# ProProject_Access_Control_Interface_2024.net
KiCad netlist of a schematic drawn in EasyEDA Pro
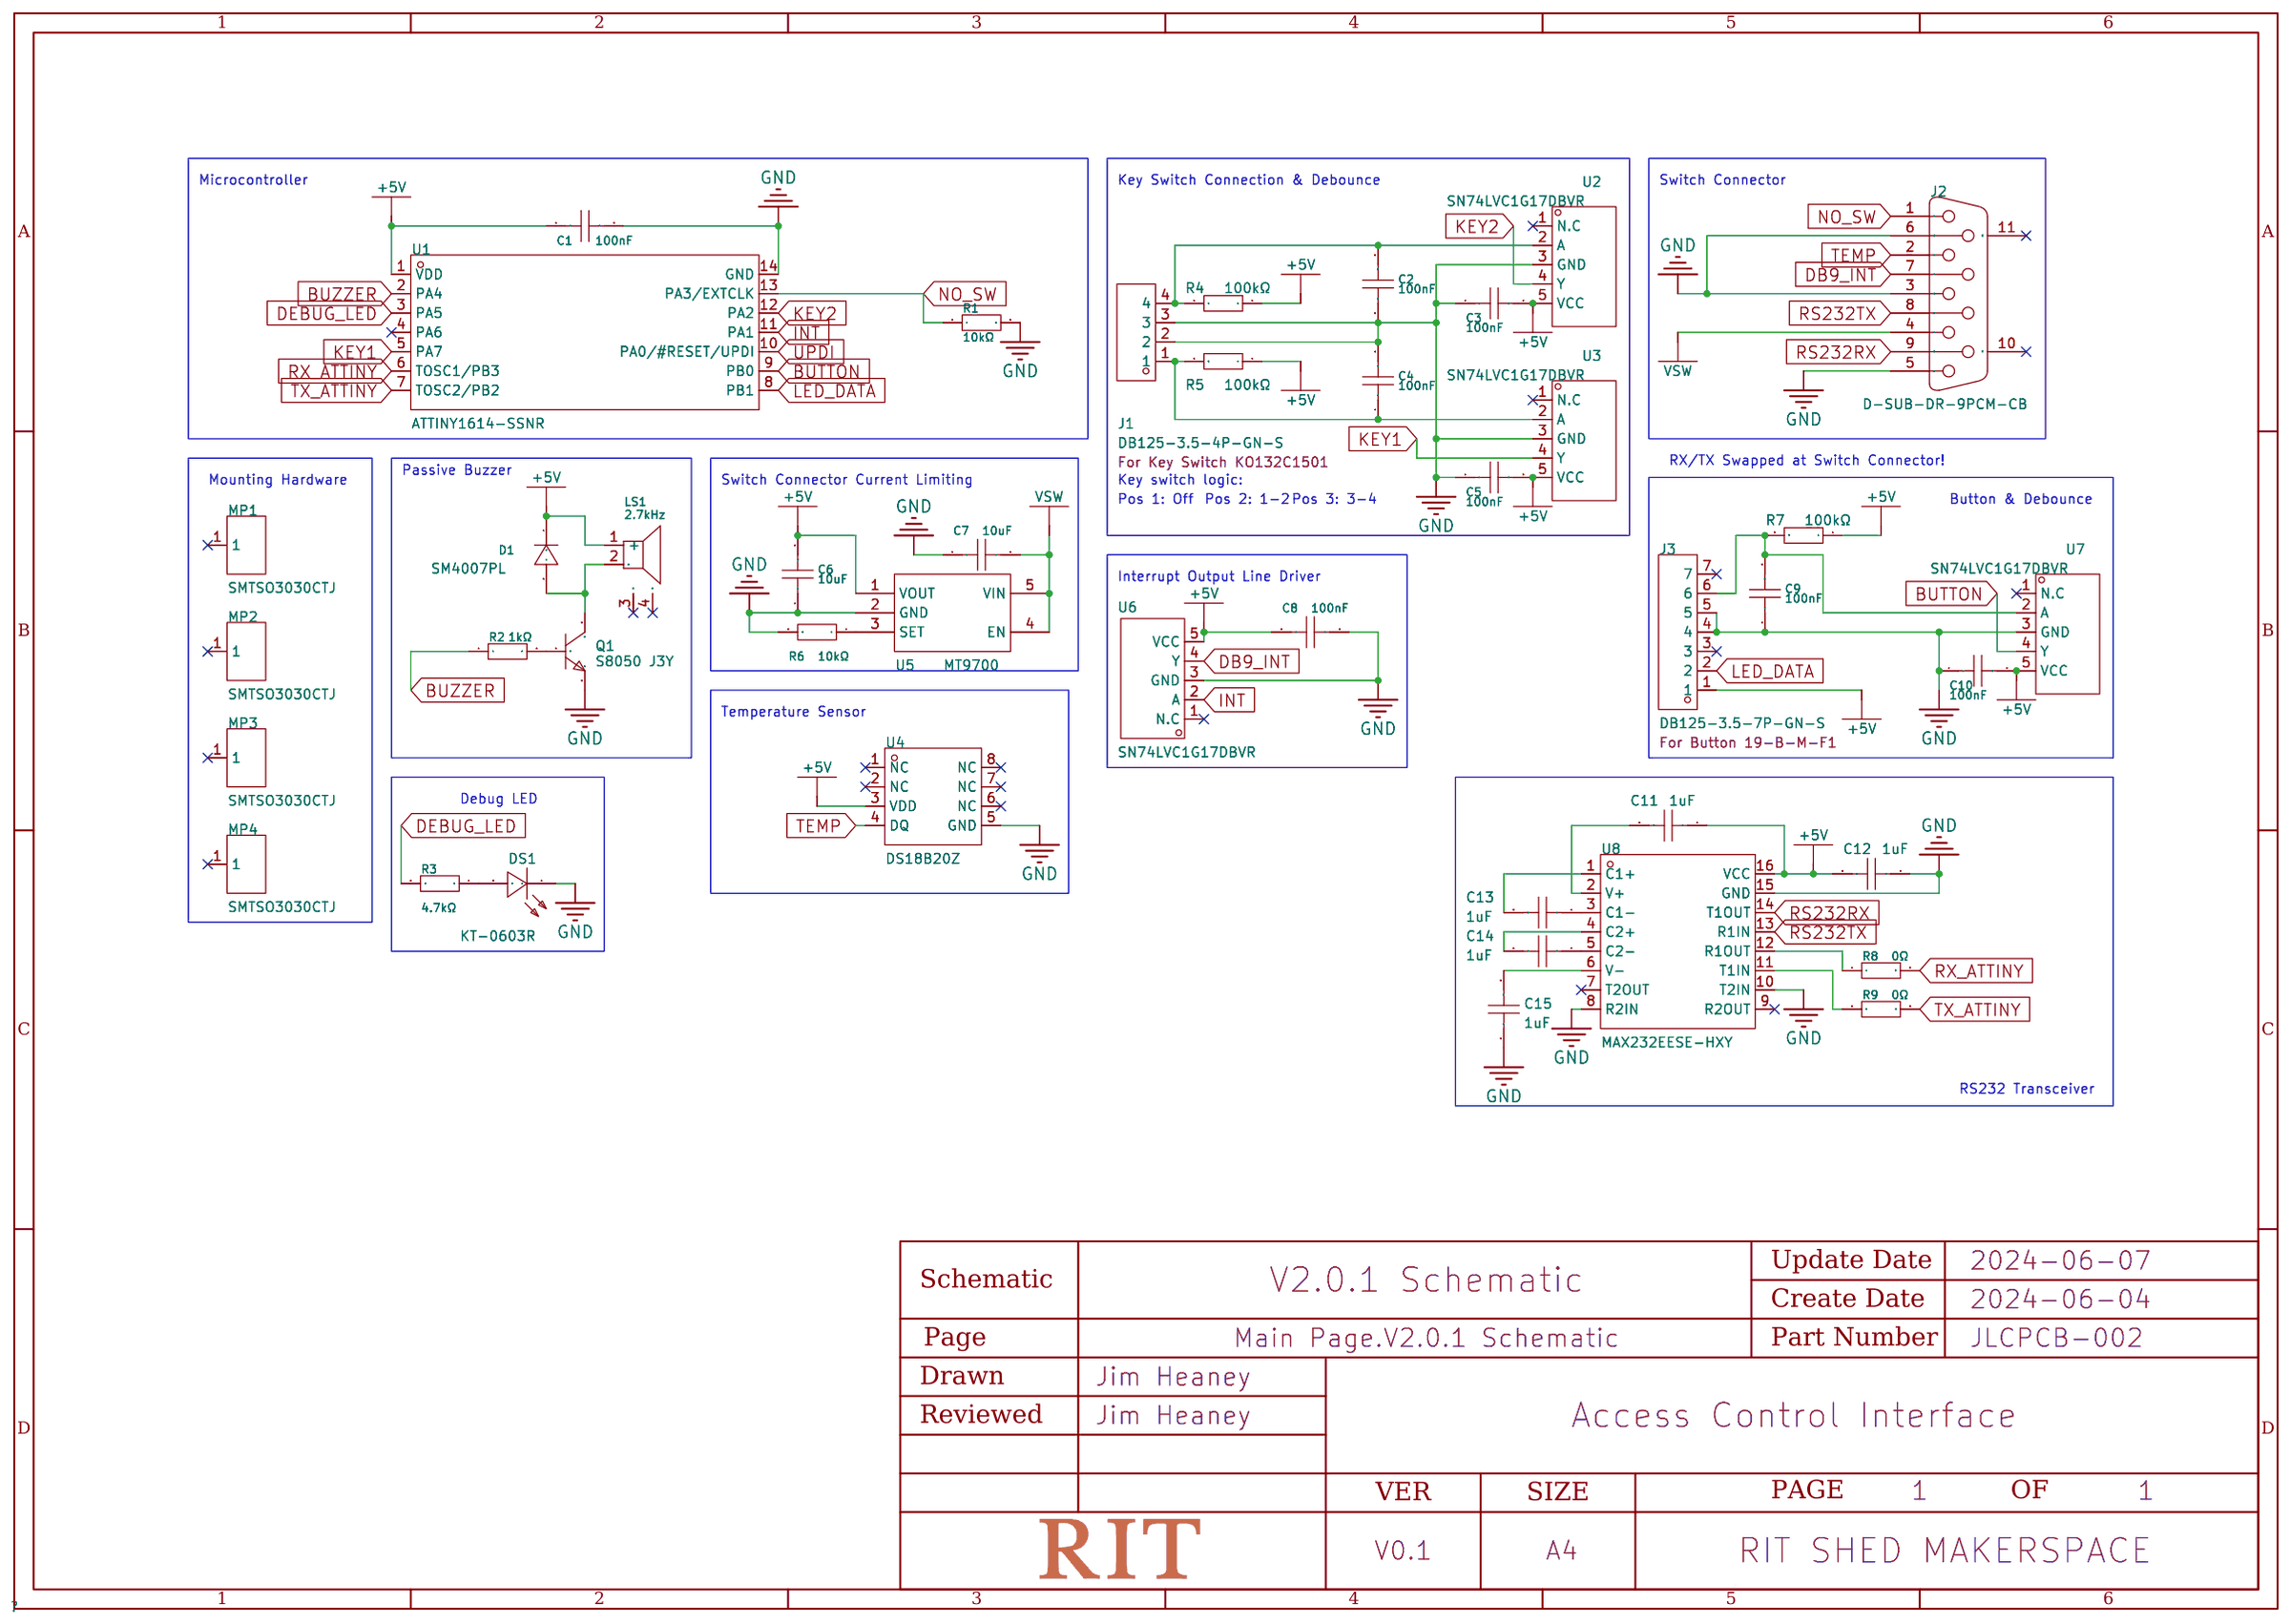
[diagram p0: schematic sheet]

(export (version "E")
  (design (tool "Eeschema 10.0.6"))
  (components
    (comp (ref "C1")
      (value "100nF")
      (footprint "easyedapro:C0603")
      (fields
        (field (name "Manufacturer Part") "CC0603KRX7R9BB104")
        (field (name "Manufacturer") "YAGEO(国巨)")
      )
      (libsource (lib "easyedapro") (part "CC0603KRX7R9BB104"))
    )
    (comp (ref "C2")
      (value "100nF")
      (footprint "easyedapro:C0603")
      (fields
        (field (name "Manufacturer Part") "CC0603KRX7R9BB104")
        (field (name "Manufacturer") "YAGEO(国巨)")
      )
      (libsource (lib "easyedapro") (part "CC0603KRX7R9BB104"))
    )
    (comp (ref "C3")
      (value "100nF")
      (footprint "easyedapro:C0603")
      (fields
        (field (name "Manufacturer Part") "CC0603KRX7R9BB104")
        (field (name "Manufacturer") "YAGEO(国巨)")
      )
      (libsource (lib "easyedapro") (part "CC0603KRX7R9BB104"))
    )
    (comp (ref "C4")
      (value "100nF")
      (footprint "easyedapro:C0603")
      (fields
        (field (name "Manufacturer Part") "CC0603KRX7R9BB104")
        (field (name "Manufacturer") "YAGEO(国巨)")
      )
      (libsource (lib "easyedapro") (part "CC0603KRX7R9BB104"))
    )
    (comp (ref "C5")
      (value "100nF")
      (footprint "easyedapro:C0603")
      (fields
        (field (name "Manufacturer Part") "CC0603KRX7R9BB104")
        (field (name "Manufacturer") "YAGEO(国巨)")
      )
      (libsource (lib "easyedapro") (part "CC0603KRX7R9BB104"))
    )
    (comp (ref "C6")
      (value "10uF")
      (footprint "easyedapro:C0603")
      (fields
        (field (name "Manufacturer Part") "CL10A106MA8NRNC")
        (field (name "Manufacturer") "SAMSUNG(三星)")
      )
      (libsource (lib "easyedapro") (part "CL10A106MA8NRNC"))
    )
    (comp (ref "C7")
      (value "10uF")
      (footprint "easyedapro:C0603")
      (fields
        (field (name "Manufacturer Part") "CL10A106MA8NRNC")
        (field (name "Manufacturer") "SAMSUNG(三星)")
      )
      (libsource (lib "easyedapro") (part "CL10A106MA8NRNC"))
    )
    (comp (ref "C8")
      (value "100nF")
      (footprint "easyedapro:C0603")
      (fields
        (field (name "Manufacturer Part") "CC0603KRX7R9BB104")
        (field (name "Manufacturer") "YAGEO(国巨)")
      )
      (libsource (lib "easyedapro") (part "CC0603KRX7R9BB104"))
    )
    (comp (ref "C9")
      (value "100nF")
      (footprint "easyedapro:C0603")
      (fields
        (field (name "Manufacturer Part") "CC0603KRX7R9BB104")
        (field (name "Manufacturer") "YAGEO(国巨)")
      )
      (libsource (lib "easyedapro") (part "CC0603KRX7R9BB104"))
    )
    (comp (ref "C10")
      (value "100nF")
      (footprint "easyedapro:C0603")
      (fields
        (field (name "Manufacturer Part") "CC0603KRX7R9BB104")
        (field (name "Manufacturer") "YAGEO(国巨)")
      )
      (libsource (lib "easyedapro") (part "CC0603KRX7R9BB104"))
    )
    (comp (ref "C11")
      (value "1uF")
      (footprint "easyedapro:C0603")
      (fields
        (field (name "Manufacturer Part") "CL10A105KB8NNNC")
        (field (name "Manufacturer") "SAMSUNG(三星)")
      )
      (libsource (lib "easyedapro") (part "CL10A105KB8NNNC"))
    )
    (comp (ref "C12")
      (value "1uF")
      (footprint "easyedapro:C0603")
      (fields
        (field (name "Manufacturer Part") "CL10A105KB8NNNC")
        (field (name "Manufacturer") "SAMSUNG(三星)")
      )
      (libsource (lib "easyedapro") (part "CL10A105KB8NNNC"))
    )
    (comp (ref "C13")
      (value "1uF")
      (footprint "easyedapro:C0603")
      (fields
        (field (name "Manufacturer Part") "CL10A105KB8NNNC")
        (field (name "Manufacturer") "SAMSUNG(三星)")
      )
      (libsource (lib "easyedapro") (part "CL10A105KB8NNNC"))
    )
    (comp (ref "C14")
      (value "1uF")
      (footprint "easyedapro:C0603")
      (fields
        (field (name "Manufacturer Part") "CL10A105KB8NNNC")
        (field (name "Manufacturer") "SAMSUNG(三星)")
      )
      (libsource (lib "easyedapro") (part "CL10A105KB8NNNC"))
    )
    (comp (ref "C15")
      (value "1uF")
      (footprint "easyedapro:C0603")
      (fields
        (field (name "Manufacturer Part") "CL10A105KB8NNNC")
        (field (name "Manufacturer") "SAMSUNG(三星)")
      )
      (libsource (lib "easyedapro") (part "CL10A105KB8NNNC"))
    )
    (comp (ref "D1")
      (value "SM4007PL")
      (footprint "easyedapro:SOD-123F_L2.8-W1.8-LS3.7-RD")
      (fields (field (name "Manufacturer") "MDD"))
      (libsource (lib "easyedapro") (part "SM4007PL"))
    )
    (comp (ref "DS1")
      (value "KT-0603R")
      (footprint "easyedapro:LED0603-RD")
      (fields (field (name "Manufacturer") "KENTO"))
      (libsource (lib "easyedapro") (part "KT-0603R"))
    )
    (comp (ref "J1")
      (value "DB125-3.5-4P-GN-S")
      (footprint "easyedapro:CONN-TH_DB125-3.5-4P-GN")
      (description "For Key Switch KO132C1501")
      (fields (field (name "Manufacturer") "DORABO(地博电气)"))
      (libsource (lib "easyedapro") (part "DB125-3.5-4P-GN"))
    )
    (comp (ref "J2")
      (value "D-SUB-DR-9PCM-CB")
      (footprint "easyedapro:DB9-TH_ID09S33E4GV00LF")
      (fields (field (name "Manufacturer") "XUNPU(讯普)"))
      (libsource (lib "easyedapro") (part "D-SUB-DR-9PCM-CB"))
    )
    (comp (ref "J3")
      (value "DB125-3.5-7P-GN-S")
      (footprint "easyedapro:CONN-TH_7P-P3.50_DORABO_DB125-3.5-7P-GN-S")
      (description "For Button 19-B-M-F1")
      (fields (field (name "Manufacturer") "DORABO(地博电气)"))
      (libsource (lib "easyedapro") (part "DB125-3.5-7P-GN-S"))
    )
    (comp (ref "LS1")
      (value "2.7kHz")
      (footprint "easyedapro:BUZ-SMD_4P-L8.5-W8.5-P8.50-TL")
      (fields (field (name "Manufacturer Part") "MLT-8540") (field (name "Manufacturer") "华能"))
      (libsource (lib "easyedapro") (part "MLT-8540"))
    )
    (comp (ref "MP1")
      (value "SMTSO3030CTJ")
      (footprint "easyedapro:SMD_BD5.6-D4.1")
      (description "specifications:M3X3 surface treatment:镀锡 Product Description:- material quality:-")
      (fields (field (name "Manufacturer") "Sinhoo(雄和远景)"))
      (libsource (lib "easyedapro") (part "SMTSO3030CTJ"))
    )
    (comp (ref "MP2")
      (value "SMTSO3030CTJ")
      (footprint "easyedapro:SMD_BD5.6-D4.1")
      (description "specifications:M3X3 surface treatment:镀锡 Product Description:- material quality:-")
      (fields (field (name "Manufacturer") "Sinhoo(雄和远景)"))
      (libsource (lib "easyedapro") (part "SMTSO3030CTJ"))
    )
    (comp (ref "MP3")
      (value "SMTSO3030CTJ")
      (footprint "easyedapro:SMD_BD5.6-D4.1")
      (description "specifications:M3X3 surface treatment:镀锡 Product Description:- material quality:-")
      (fields (field (name "Manufacturer") "Sinhoo(雄和远景)"))
      (libsource (lib "easyedapro") (part "SMTSO3030CTJ"))
    )
    (comp (ref "MP4")
      (value "SMTSO3030CTJ")
      (footprint "easyedapro:SMD_BD5.6-D4.1")
      (description "specifications:M3X3 surface treatment:镀锡 Product Description:- material quality:-")
      (fields (field (name "Manufacturer") "Sinhoo(雄和远景)"))
      (libsource (lib "easyedapro") (part "SMTSO3030CTJ"))
    )
    (comp (ref "Q1")
      (value "S8050 J3Y")
      (footprint "easyedapro:SOT-23-3_L3.0-W1.7-P0.95-LS2.9-BR")
      (fields (field (name "Manufacturer") "CJ(江苏长电/长晶)"))
      (libsource (lib "easyedapro") (part "S8050_C2146"))
    )
    (comp (ref "R1")
      (value "10kΩ")
      (footprint "easyedapro:R0603")
      (fields
        (field (name "Manufacturer Part") "0603WAF1002T5E")
        (field (name "Manufacturer") "UNI-ROYAL(厚声)")
      )
      (libsource (lib "easyedapro") (part "0603WAF1002T5E"))
    )
    (comp (ref "R2")
      (value "1kΩ")
      (footprint "easyedapro:R0603")
      (fields
        (field (name "Manufacturer Part") "0603WAF1001T5E")
        (field (name "Manufacturer") "UNI-ROYAL(厚声)")
      )
      (libsource (lib "easyedapro") (part "0603WAF1001T5E"))
    )
    (comp (ref "R3")
      (value "4.7kΩ")
      (footprint "easyedapro:R0603")
      (fields
        (field (name "Manufacturer Part") "0603WAF4701T5E")
        (field (name "Manufacturer") "UNI-ROYAL(厚声)")
      )
      (libsource (lib "easyedapro") (part "0603WAF4701T5E"))
    )
    (comp (ref "R4")
      (value "100kΩ")
      (footprint "easyedapro:R0603")
      (fields
        (field (name "Manufacturer Part") "0603WAF1003T5E")
        (field (name "Manufacturer") "UNI-ROYAL(厚声)")
      )
      (libsource (lib "easyedapro") (part "0603WAF1003T5E"))
    )
    (comp (ref "R5")
      (value "100kΩ")
      (footprint "easyedapro:R0603")
      (fields
        (field (name "Manufacturer Part") "0603WAF1003T5E")
        (field (name "Manufacturer") "UNI-ROYAL(厚声)")
      )
      (libsource (lib "easyedapro") (part "0603WAF1003T5E"))
    )
    (comp (ref "R6")
      (value "10kΩ")
      (footprint "easyedapro:R0603")
      (fields
        (field (name "Manufacturer Part") "0603WAF1002T5E")
        (field (name "Manufacturer") "UNI-ROYAL(厚声)")
      )
      (libsource (lib "easyedapro") (part "0603WAF1002T5E"))
    )
    (comp (ref "R7")
      (value "100kΩ")
      (footprint "easyedapro:R0603")
      (fields
        (field (name "Manufacturer Part") "0603WAF1003T5E")
        (field (name "Manufacturer") "UNI-ROYAL(厚声)")
      )
      (libsource (lib "easyedapro") (part "0603WAF1003T5E"))
    )
    (comp (ref "R8")
      (value "0Ω")
      (footprint "easyedapro:R1206")
      (fields
        (field (name "Manufacturer Part") "1206W4F0000T5E")
        (field (name "Manufacturer") "UNI-ROYAL(厚声)")
      )
      (libsource (lib "easyedapro") (part "1206W4F0000T5E"))
    )
    (comp (ref "R9")
      (value "0Ω")
      (footprint "easyedapro:R1206")
      (fields
        (field (name "Manufacturer Part") "1206W4F0000T5E")
        (field (name "Manufacturer") "UNI-ROYAL(厚声)")
      )
      (libsource (lib "easyedapro") (part "1206W4F0000T5E"))
    )
    (comp (ref "U1")
      (value "ATTINY1614-SSNR")
      (footprint "easyedapro:SOIC-14_L8.7-W3.9-P1.27-LS6.0-BL")
      (fields (field (name "Manufacturer") "MICROCHIP(美国微芯)"))
      (libsource (lib "easyedapro") (part "ATTINY1614-SSNR"))
    )
    (comp (ref "U2")
      (value "SN74LVC1G17DBVR")
      (footprint "easyedapro:SOT-23-5_L3.0-W1.7-P0.95-LS2.8-BR")
      (fields (field (name "Manufacturer") "TI(德州仪器)"))
      (libsource (lib "easyedapro") (part "SN74LVC1G17DBVR"))
    )
    (comp (ref "U3")
      (value "SN74LVC1G17DBVR")
      (footprint "easyedapro:SOT-23-5_L3.0-W1.7-P0.95-LS2.8-BR")
      (fields (field (name "Manufacturer") "TI(德州仪器)"))
      (libsource (lib "easyedapro") (part "SN74LVC1G17DBVR"))
    )
    (comp (ref "U4")
      (value "DS18B20Z")
      (footprint "easyedapro:SOP-8_L4.9-W3.9-P1.27-LS6.0-BL")
      (description "Resolution:±0.4°C Resolution:±0.4°C Supply Voltage:2.5V~5.5V Supply Voltage:2.5V~5.5V")
      (fields (field (name "Manufacturer") "UMW(友台半导体)"))
      (libsource (lib "easyedapro") (part "DS18B20Z"))
    )
    (comp (ref "U5")
      (value "MT9700")
      (footprint "easyedapro:SOT-23-5_L3.0-W1.7-P0.95-LS2.8-BR")
      (fields (field (name "Manufacturer") "西安航天民芯"))
      (libsource (lib "easyedapro") (part "MT9700"))
    )
    (comp (ref "U6")
      (value "SN74LVC1G17DBVR")
      (footprint "easyedapro:SOT-23-5_L3.0-W1.7-P0.95-LS2.8-BR")
      (fields (field (name "Manufacturer") "TI(德州仪器)"))
      (libsource (lib "easyedapro") (part "SN74LVC1G17DBVR"))
    )
    (comp (ref "U7")
      (value "SN74LVC1G17DBVR")
      (footprint "easyedapro:SOT-23-5_L3.0-W1.7-P0.95-LS2.8-BR")
      (fields (field (name "Manufacturer") "TI(德州仪器)"))
      (libsource (lib "easyedapro") (part "SN74LVC1G17DBVR"))
    )
    (comp (ref "U8")
      (value "MAX232EESE-HXY")
      (footprint "easyedapro:SOP-16_L9.9-W3.9-P1.27-LS6.0-BL")
      (description "Driver/receiver:2/2 Data Rate:120Kbps Data Rate:120Kbps Supply Voltage:5V Supply Voltage:5V")
      (fields (field (name "Manufacturer") "HXY MOSFET(华轩阳电子)"))
      (libsource (lib "easyedapro") (part "MAX232EESE-HXY"))
    )
  )
  (nets
    (net (code "1") (name "+5V") (class "Default")
      (node (ref "C1") (pin "1") (pinfunction "1_1") (pintype "input"))
      (node (ref "C10") (pin "2") (pinfunction "2_2") (pintype "input"))
      (node (ref "C11") (pin "1") (pinfunction "1_1") (pintype "unspecified"))
      (node (ref "C12") (pin "2") (pinfunction "2_2") (pintype "unspecified"))
      (node (ref "C3") (pin "2") (pinfunction "2_2") (pintype "input"))
      (node (ref "C5") (pin "2") (pinfunction "2_2") (pintype "input"))
      (node (ref "C6") (pin "2") (pinfunction "2_2") (pintype "input"))
      (node (ref "C8") (pin "1") (pinfunction "1_1") (pintype "input"))
      (node (ref "D1") (pin "1") (pinfunction "C_1") (pintype "input"))
      (node (ref "J3") (pin "1") (pinfunction "1_1") (pintype "unspecified"))
      (node (ref "LS1") (pin "1") (pinfunction "+_1") (pintype "input"))
      (node (ref "R4") (pin "1") (pinfunction "1_1") (pintype "input"))
      (node (ref "R5") (pin "1") (pinfunction "1_1") (pintype "input"))
      (node (ref "R7") (pin "1") (pinfunction "1_1") (pintype "input"))
      (node (ref "U1") (pin "1") (pinfunction "VDD_1") (pintype "input"))
      (node (ref "U2") (pin "5") (pinfunction "VCC_5") (pintype "input"))
      (node (ref "U3") (pin "5") (pinfunction "VCC_5") (pintype "input"))
      (node (ref "U4") (pin "3") (pinfunction "VDD_3") (pintype "unspecified"))
      (node (ref "U5") (pin "1") (pinfunction "VOUT_1") (pintype "unspecified"))
      (node (ref "U6") (pin "5") (pinfunction "VCC_5") (pintype "input"))
      (node (ref "U7") (pin "5") (pinfunction "VCC_5") (pintype "input"))
      (node (ref "U8") (pin "16") (pinfunction "VCC_16") (pintype "unspecified"))
    )
    (net (code "2") (name "BUTTON") (class "Default")
      (node (ref "U1") (pin "9") (pinfunction "PB0_9") (pintype "input"))
      (node (ref "U7") (pin "4") (pinfunction "Y_4") (pintype "input"))
    )
    (net (code "3") (name "BUZZER") (class "Default")
      (node (ref "R2") (pin "1") (pinfunction "1_1") (pintype "input"))
      (node (ref "U1") (pin "2") (pinfunction "PA4_2") (pintype "input"))
    )
    (net (code "4") (name "DB9_INT") (class "Default")
      (node (ref "J2") (pin "7") (pinfunction "7_7") (pintype "input"))
      (node (ref "U6") (pin "4") (pinfunction "Y_4") (pintype "input"))
    )
    (net (code "5") (name "DEBUG_LED") (class "Default")
      (node (ref "R3") (pin "2") (pinfunction "2_2") (pintype "input"))
      (node (ref "U1") (pin "3") (pinfunction "PA5_3") (pintype "input"))
    )
    (net (code "6") (name "GND") (class "Default")
      (node (ref "C1") (pin "2") (pinfunction "2_2") (pintype "input"))
      (node (ref "C10") (pin "1") (pinfunction "1_1") (pintype "input"))
      (node (ref "C12") (pin "1") (pinfunction "1_1") (pintype "unspecified"))
      (node (ref "C15") (pin "1") (pinfunction "1_1") (pintype "unspecified"))
      (node (ref "C2") (pin "1") (pinfunction "1_1") (pintype "input"))
      (node (ref "C3") (pin "1") (pinfunction "1_1") (pintype "input"))
      (node (ref "C4") (pin "2") (pinfunction "2_2") (pintype "input"))
      (node (ref "C5") (pin "1") (pinfunction "1_1") (pintype "input"))
      (node (ref "C6") (pin "1") (pinfunction "1_1") (pintype "input"))
      (node (ref "C7") (pin "2") (pinfunction "2_2") (pintype "input"))
      (node (ref "C8") (pin "2") (pinfunction "2_2") (pintype "input"))
      (node (ref "C9") (pin "1") (pinfunction "1_1") (pintype "input"))
      (node (ref "DS1") (pin "1") (pinfunction "K_1") (pintype "input"))
      (node (ref "J1") (pin "2") (pinfunction "2_2") (pintype "unspecified"))
      (node (ref "J1") (pin "3") (pinfunction "3_3") (pintype "unspecified"))
      (node (ref "J2") (pin "3") (pinfunction "3_3") (pintype "input"))
      (node (ref "J2") (pin "5") (pinfunction "5_5") (pintype "input"))
      (node (ref "J2") (pin "6") (pinfunction "6_6") (pintype "input"))
      (node (ref "J3") (pin "4") (pinfunction "4_4") (pintype "unspecified"))
      (node (ref "J3") (pin "5") (pinfunction "5_5") (pintype "unspecified"))
      (node (ref "Q1") (pin "2") (pinfunction "E_2") (pintype "unspecified"))
      (node (ref "R1") (pin "2") (pinfunction "2_2") (pintype "input"))
      (node (ref "R6") (pin "2") (pinfunction "2_2") (pintype "input"))
      (node (ref "U1") (pin "14") (pinfunction "GND_14") (pintype "input"))
      (node (ref "U2") (pin "3") (pinfunction "GND_3") (pintype "input"))
      (node (ref "U3") (pin "3") (pinfunction "GND_3") (pintype "input"))
      (node (ref "U4") (pin "5") (pinfunction "GND_5") (pintype "unspecified"))
      (node (ref "U5") (pin "2") (pinfunction "GND_2") (pintype "unspecified"))
      (node (ref "U6") (pin "3") (pinfunction "GND_3") (pintype "input"))
      (node (ref "U7") (pin "3") (pinfunction "GND_3") (pintype "input"))
      (node (ref "U8") (pin "10") (pinfunction "T2IN_10") (pintype "unspecified"))
      (node (ref "U8") (pin "15") (pinfunction "GND_15") (pintype "unspecified"))
      (node (ref "U8") (pin "8") (pinfunction "R2IN_8") (pintype "unspecified"))
    )
    (net (code "7") (name "INT") (class "Default")
      (node (ref "U1") (pin "11") (pinfunction "PA1_11") (pintype "input"))
      (node (ref "U6") (pin "2") (pinfunction "A_2") (pintype "input"))
    )
    (net (code "8") (name "KEY1") (class "Default")
      (node (ref "U1") (pin "5") (pinfunction "PA7_5") (pintype "input"))
      (node (ref "U3") (pin "4") (pinfunction "Y_4") (pintype "input"))
    )
    (net (code "9") (name "KEY2") (class "Default")
      (node (ref "U1") (pin "12") (pinfunction "PA2_12") (pintype "input"))
      (node (ref "U2") (pin "4") (pinfunction "Y_4") (pintype "input"))
    )
    (net (code "10") (name "LED_DATA") (class "Default")
      (node (ref "J3") (pin "2") (pinfunction "2_2") (pintype "unspecified"))
      (node (ref "U1") (pin "8") (pinfunction "PB1_8") (pintype "input"))
    )
    (net (code "11") (name "NO_SW") (class "Default")
      (node (ref "J2") (pin "1") (pinfunction "1_1") (pintype "input"))
      (node (ref "R1") (pin "1") (pinfunction "1_1") (pintype "input"))
      (node (ref "U1") (pin "13") (pinfunction "PA3/EXTCLK_13") (pintype "input"))
    )
    (net (code "12") (name "Net-(D1-A)") (class "Default")
      (node (ref "D1") (pin "2") (pinfunction "A_2") (pintype "input"))
      (node (ref "LS1") (pin "2") (pinfunction "2_2") (pintype "input"))
      (node (ref "Q1") (pin "3") (pinfunction "C_3") (pintype "unspecified"))
    )
    (net (code "13") (name "Net-(DS1-A)") (class "Default")
      (node (ref "DS1") (pin "2") (pinfunction "A_2") (pintype "input"))
      (node (ref "R3") (pin "1") (pinfunction "1_1") (pintype "input"))
    )
    (net (code "14") (name "Net-(Q1-B)") (class "Default")
      (node (ref "Q1") (pin "1") (pinfunction "B_1") (pintype "unspecified"))
      (node (ref "R2") (pin "2") (pinfunction "2_2") (pintype "input"))
    )
    (net (code "15") (name "Net-(U2-A)") (class "Default")
      (node (ref "C2") (pin "2") (pinfunction "2_2") (pintype "input"))
      (node (ref "J1") (pin "4") (pinfunction "4_4") (pintype "unspecified"))
      (node (ref "R4") (pin "2") (pinfunction "2_2") (pintype "input"))
      (node (ref "U2") (pin "2") (pinfunction "A_2") (pintype "input"))
    )
    (net (code "16") (name "Net-(U3-A)") (class "Default")
      (node (ref "C4") (pin "1") (pinfunction "1_1") (pintype "input"))
      (node (ref "J1") (pin "1") (pinfunction "1_1") (pintype "unspecified"))
      (node (ref "R5") (pin "2") (pinfunction "2_2") (pintype "input"))
      (node (ref "U3") (pin "2") (pinfunction "A_2") (pintype "input"))
    )
    (net (code "17") (name "Net-(U5-SET)") (class "Default")
      (node (ref "R6") (pin "1") (pinfunction "1_1") (pintype "input"))
      (node (ref "U5") (pin "3") (pinfunction "SET_3") (pintype "unspecified"))
    )
    (net (code "18") (name "Net-(U7-A)") (class "Default")
      (node (ref "C9") (pin "2") (pinfunction "2_2") (pintype "input"))
      (node (ref "J3") (pin "6") (pinfunction "6_6") (pintype "unspecified"))
      (node (ref "R7") (pin "2") (pinfunction "2_2") (pintype "input"))
      (node (ref "U7") (pin "2") (pinfunction "A_2") (pintype "input"))
    )
    (net (code "19") (name "Net-(U8-C1+)") (class "Default")
      (node (ref "C13") (pin "2") (pinfunction "2_2") (pintype "unspecified"))
      (node (ref "U8") (pin "1") (pinfunction "C1+_1") (pintype "unspecified"))
    )
    (net (code "20") (name "Net-(U8-C1-)") (class "Default")
      (node (ref "C13") (pin "1") (pinfunction "1_1") (pintype "unspecified"))
      (node (ref "U8") (pin "3") (pinfunction "C1-_3") (pintype "unspecified"))
    )
    (net (code "21") (name "Net-(U8-C2+)") (class "Default")
      (node (ref "C14") (pin "2") (pinfunction "2_2") (pintype "unspecified"))
      (node (ref "U8") (pin "4") (pinfunction "C2+_4") (pintype "unspecified"))
    )
    (net (code "22") (name "Net-(U8-C2-)") (class "Default")
      (node (ref "C14") (pin "1") (pinfunction "1_1") (pintype "unspecified"))
      (node (ref "U8") (pin "5") (pinfunction "C2-_5") (pintype "unspecified"))
    )
    (net (code "23") (name "Net-(U8-R1OUT)") (class "Default")
      (node (ref "R8") (pin "1") (pinfunction "1_1") (pintype "input"))
      (node (ref "U8") (pin "12") (pinfunction "R1OUT_12") (pintype "unspecified"))
    )
    (net (code "24") (name "Net-(U8-T1IN)") (class "Default")
      (node (ref "R9") (pin "1") (pinfunction "1_1") (pintype "input"))
      (node (ref "U8") (pin "11") (pinfunction "T1IN_11") (pintype "unspecified"))
    )
    (net (code "25") (name "Net-(U8-V+)") (class "Default")
      (node (ref "C11") (pin "2") (pinfunction "2_2") (pintype "unspecified"))
      (node (ref "U8") (pin "2") (pinfunction "V+_2") (pintype "unspecified"))
    )
    (net (code "26") (name "Net-(U8-V-)") (class "Default")
      (node (ref "C15") (pin "2") (pinfunction "2_2") (pintype "unspecified"))
      (node (ref "U8") (pin "6") (pinfunction "V-_6") (pintype "unspecified"))
    )
    (net (code "27") (name "RS232RX") (class "Default")
      (node (ref "J2") (pin "9") (pinfunction "9_9") (pintype "input"))
      (node (ref "U8") (pin "14") (pinfunction "T1OUT_14") (pintype "unspecified"))
    )
    (net (code "28") (name "RS232TX") (class "Default")
      (node (ref "J2") (pin "8") (pinfunction "8_8") (pintype "input"))
      (node (ref "U8") (pin "13") (pinfunction "R1IN_13") (pintype "unspecified"))
    )
    (net (code "29") (name "RX_ATTINY") (class "Default")
      (node (ref "R8") (pin "2") (pinfunction "2_2") (pintype "input"))
      (node (ref "U1") (pin "6") (pinfunction "TOSC1/PB3_6") (pintype "input"))
    )
    (net (code "30") (name "TEMP") (class "Default")
      (node (ref "J2") (pin "2") (pinfunction "2_2") (pintype "input"))
      (node (ref "U4") (pin "4") (pinfunction "DQ_4") (pintype "unspecified"))
    )
    (net (code "31") (name "TX_ATTINY") (class "Default")
      (node (ref "R9") (pin "2") (pinfunction "2_2") (pintype "input"))
      (node (ref "U1") (pin "7") (pinfunction "TOSC2/PB2_7") (pintype "input"))
    )
    (net (code "32") (name "UPDI") (class "Default")
      (node (ref "U1") (pin "10") (pinfunction "PA0/#RESET/UPDI_10") (pintype "input"))
    )
    (net (code "33") (name "VSW") (class "Default")
      (node (ref "C7") (pin "1") (pinfunction "1_1") (pintype "input"))
      (node (ref "J2") (pin "4") (pinfunction "4_4") (pintype "input"))
      (node (ref "U5") (pin "4") (pinfunction "EN_4") (pintype "unspecified"))
      (node (ref "U5") (pin "5") (pinfunction "VIN_5") (pintype "unspecified"))
    )
    (net (code "34") (name "unconnected-(J2-MH1-Pad10)") (class "Default")
      (node (ref "J2") (pin "10") (pinfunction "MH1_10") (pintype "input+no_connect"))
    )
    (net (code "35") (name "unconnected-(J2-MH2-Pad11)") (class "Default")
      (node (ref "J2") (pin "11") (pinfunction "MH2_11") (pintype "input+no_connect"))
    )
    (net (code "36") (name "unconnected-(J3-Pad3)") (class "Default")
      (node (ref "J3") (pin "3") (pinfunction "3_3") (pintype "unspecified+no_connect"))
    )
    (net (code "37") (name "unconnected-(J3-Pad7)") (class "Default")
      (node (ref "J3") (pin "7") (pinfunction "7_7") (pintype "unspecified+no_connect"))
    )
    (net (code "38") (name "unconnected-(LS1-NC-Pad3)") (class "Default")
      (node (ref "LS1") (pin "3") (pinfunction "NC_3") (pintype "input+no_connect"))
    )
    (net (code "39") (name "unconnected-(LS1-NC-Pad4)") (class "Default")
      (node (ref "LS1") (pin "4") (pinfunction "NC_4") (pintype "input+no_connect"))
    )
    (net (code "40") (name "unconnected-(MP1-Pad1)") (class "Default")
      (node (ref "MP1") (pin "1") (pinfunction "1_1") (pintype "unspecified+no_connect"))
    )
    (net (code "41") (name "unconnected-(MP2-Pad1)") (class "Default")
      (node (ref "MP2") (pin "1") (pinfunction "1_1") (pintype "unspecified+no_connect"))
    )
    (net (code "42") (name "unconnected-(MP3-Pad1)") (class "Default")
      (node (ref "MP3") (pin "1") (pinfunction "1_1") (pintype "unspecified+no_connect"))
    )
    (net (code "43") (name "unconnected-(MP4-Pad1)") (class "Default")
      (node (ref "MP4") (pin "1") (pinfunction "1_1") (pintype "unspecified+no_connect"))
    )
    (net (code "44") (name "unconnected-(U1-PA6-Pad4)") (class "Default")
      (node (ref "U1") (pin "4") (pinfunction "PA6_4") (pintype "input+no_connect"))
    )
    (net (code "45") (name "unconnected-(U2-N.C-Pad1)") (class "Default")
      (node (ref "U2") (pin "1") (pinfunction "N.C_1") (pintype "input+no_connect"))
    )
    (net (code "46") (name "unconnected-(U3-N.C-Pad1)") (class "Default")
      (node (ref "U3") (pin "1") (pinfunction "N.C_1") (pintype "input+no_connect"))
    )
    (net (code "47") (name "unconnected-(U4-NC-Pad1)") (class "Default")
      (node (ref "U4") (pin "1") (pinfunction "NC_1") (pintype "unspecified+no_connect"))
    )
    (net (code "48") (name "unconnected-(U4-NC-Pad2)") (class "Default")
      (node (ref "U4") (pin "2") (pinfunction "NC_2") (pintype "unspecified+no_connect"))
    )
    (net (code "49") (name "unconnected-(U4-NC-Pad6)") (class "Default")
      (node (ref "U4") (pin "6") (pinfunction "NC_6") (pintype "unspecified+no_connect"))
    )
    (net (code "50") (name "unconnected-(U4-NC-Pad7)") (class "Default")
      (node (ref "U4") (pin "7") (pinfunction "NC_7") (pintype "unspecified+no_connect"))
    )
    (net (code "51") (name "unconnected-(U4-NC-Pad8)") (class "Default")
      (node (ref "U4") (pin "8") (pinfunction "NC_8") (pintype "unspecified+no_connect"))
    )
    (net (code "52") (name "unconnected-(U6-N.C-Pad1)") (class "Default")
      (node (ref "U6") (pin "1") (pinfunction "N.C_1") (pintype "input+no_connect"))
    )
    (net (code "53") (name "unconnected-(U7-N.C-Pad1)") (class "Default")
      (node (ref "U7") (pin "1") (pinfunction "N.C_1") (pintype "input+no_connect"))
    )
    (net (code "54") (name "unconnected-(U8-R2OUT-Pad9)") (class "Default")
      (node (ref "U8") (pin "9") (pinfunction "R2OUT_9") (pintype "unspecified+no_connect"))
    )
    (net (code "55") (name "unconnected-(U8-T2OUT-Pad7)") (class "Default")
      (node (ref "U8") (pin "7") (pinfunction "T2OUT_7") (pintype "unspecified+no_connect"))
    )
  )
)
